# Speaker_LM4818.net
KiCad netlist of a schematic drawn in Altium Designer
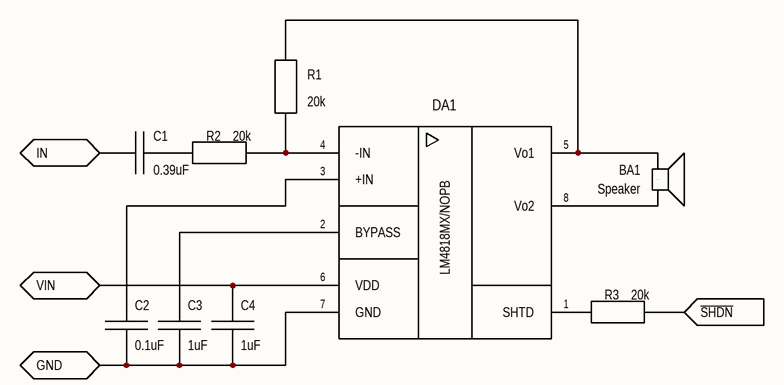
[diagram p0: Speaker LM4818.SchDoc]

(export (version "E")
  (design (tool "Eeschema 10.0.6"))
  (components
    (comp (ref "BA1")
      (value "Speaker")
      (footprint "Speaker wires")
      (description "Speaker wires")
      (libsource (lib "Electro-Mechanical") (part "Speaker wires"))
    )
    (comp (ref "C1")
      (value "0.39uF")
      (footprint "CAPC1608L")
      (description "Capacitor Ceramic 0.39uF 10V 0603(1608)")
      (fields (field (name "TOLERANCE") "±10%") (field (name "VOLTAGE") "10V"))
      (libsource (lib "Capacitors") (part "Capacitor Ceramic 0.39uF 10V 0603(1608)"))
    )
    (comp (ref "C2")
      (value "0.1uF")
      (footprint "CAPC1608L")
      (description "Capacitor Ceramic 0.1uF 25V 0603(1608)")
      (fields (field (name "TOLERANCE") "±10%") (field (name "VOLTAGE") "25V"))
      (libsource (lib "Capacitors") (part "Capacitor Ceramic 0.1uF 25V 0603(1608)"))
    )
    (comp (ref "C3")
      (value "1uF")
      (footprint "CAPC1608L")
      (description "Capacitor Ceramic 1uF 25V 0603(1608)")
      (fields (field (name "TOLERANCE") "±10%") (field (name "VOLTAGE") "25V"))
      (libsource (lib "Capacitors") (part "Capacitor Ceramic 1uF 25V 0603(1608)"))
    )
    (comp (ref "C4")
      (value "1uF")
      (footprint "CAPC1608L")
      (description "Capacitor Ceramic 1uF 25V 0603(1608)")
      (fields (field (name "TOLERANCE") "±10%") (field (name "VOLTAGE") "25V"))
      (libsource (lib "Capacitors") (part "Capacitor Ceramic 1uF 25V 0603(1608)"))
    )
    (comp (ref "DA1")
      (value "LM4818MX/NOPB")
      (footprint "SOIC-8")
      (description "Audio Power Amplifier with Shutdown  Mode")
      (fields (field (name "MANUFACTURER") "Texas Instruments"))
      (libsource (lib "ICs") (part "LM4818MX/NOPB"))
    )
    (comp (ref "R1")
      (value "20k")
      (footprint "RESC1608L")
      (description "Resistor Ceramic 20k 0.1W 0603(1608)")
      (fields (field (name "TOLERANCE") "±5%") (field (name "POWER") "0.1W"))
      (libsource (lib "Resistors") (part "Resistor Ceramic 20k 0.1W 0603(1608)_1"))
    )
    (comp (ref "R2")
      (value "20k")
      (footprint "RESC1608L")
      (description "Resistor Ceramic 20k 0.1W 0603(1608)")
      (fields (field (name "TOLERANCE") "±5%") (field (name "POWER") "0.1W"))
      (libsource (lib "Resistors") (part "Resistor Ceramic 20k 0.1W 0603(1608)_1"))
    )
    (comp (ref "R3")
      (value "20k")
      (footprint "RESC1608L")
      (description "Resistor Ceramic 20k 0.1W 0603(1608)")
      (fields (field (name "TOLERANCE") "±5%") (field (name "POWER") "0.1W"))
      (libsource (lib "Resistors") (part "Resistor Ceramic 20k 0.1W 0603(1608)_1"))
    )
  )
  (nets
    (net (code "1") (name "/GND") (class "Default")
      (node (ref "C2") (pin "2") (pinfunction "2_2") (pintype "passive"))
      (node (ref "C3") (pin "2") (pinfunction "2_2") (pintype "passive"))
      (node (ref "C4") (pin "2") (pinfunction "2_2") (pintype "passive"))
      (node (ref "DA1") (pin "7") (pinfunction "GND_7") (pintype "passive"))
    )
    (net (code "2") (name "/IN") (class "Default")
      (node (ref "C1") (pin "1") (pinfunction "1_1") (pintype "passive"))
    )
    (net (code "3") (name "/VIN") (class "Default")
      (node (ref "C4") (pin "1") (pinfunction "1_1") (pintype "passive"))
      (node (ref "DA1") (pin "6") (pinfunction "VDD_6") (pintype "passive"))
    )
    (net (code "4") (name "/~{SHDN}") (class "Default")
      (node (ref "R3") (pin "2") (pinfunction "2_2") (pintype "passive"))
    )
    (net (code "5") (name "Net-(BA1-+)") (class "Default")
      (node (ref "BA1") (pin "1") (pinfunction "+_1") (pintype "passive"))
      (node (ref "DA1") (pin "5") (pinfunction "Vo1_5") (pintype "passive"))
      (node (ref "R1") (pin "1") (pinfunction "1_1") (pintype "passive"))
    )
    (net (code "6") (name "Net-(BA1--)") (class "Default")
      (node (ref "BA1") (pin "2") (pinfunction "-_2") (pintype "passive"))
      (node (ref "DA1") (pin "8") (pinfunction "Vo2_8") (pintype "passive"))
    )
    (net (code "7") (name "Net-(C1-Pad2)") (class "Default")
      (node (ref "C1") (pin "2") (pinfunction "2_2") (pintype "passive"))
      (node (ref "R2") (pin "1") (pinfunction "1_1") (pintype "passive"))
    )
    (net (code "8") (name "Net-(DA1-+IN)") (class "Default")
      (node (ref "C2") (pin "1") (pinfunction "1_1") (pintype "passive"))
      (node (ref "DA1") (pin "3") (pinfunction "+IN_3") (pintype "passive"))
    )
    (net (code "9") (name "Net-(DA1--IN)") (class "Default")
      (node (ref "DA1") (pin "4") (pinfunction "-IN_4") (pintype "passive"))
      (node (ref "R1") (pin "2") (pinfunction "2_2") (pintype "passive"))
      (node (ref "R2") (pin "2") (pinfunction "2_2") (pintype "passive"))
    )
    (net (code "10") (name "Net-(DA1-BYPASS)") (class "Default")
      (node (ref "C3") (pin "1") (pinfunction "1_1") (pintype "passive"))
      (node (ref "DA1") (pin "2") (pinfunction "BYPASS_2") (pintype "passive"))
    )
    (net (code "11") (name "Net-(DA1-SHTD)") (class "Default")
      (node (ref "DA1") (pin "1") (pinfunction "SHTD_1") (pintype "passive"))
      (node (ref "R3") (pin "1") (pinfunction "1_1") (pintype "passive"))
    )
  )
)
